# servo_controller.net
KiCad netlist of a schematic drawn in EAGLE
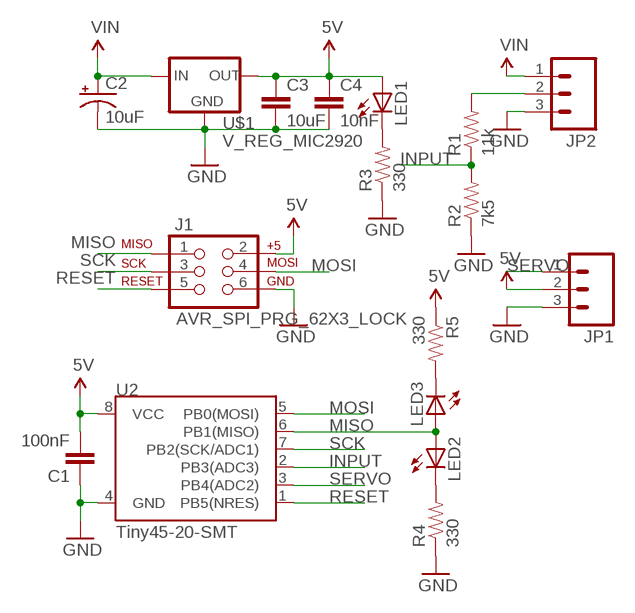
[diagram p0: schematic, sheet 1]

(export (version "E")
  (design (tool "Eeschema 10.0.6"))
  (components
    (comp (ref "C1")
      (value "100nF")
      (footprint "eagle-import:0603-CAP")
      (libsource (lib "eagle-import") (part "CAP0603-CAP"))
    )
    (comp (ref "C2")
      (value "10uF")
      (footprint "eagle-import:PANASONIC_B")
      (libsource (lib "eagle-import") (part "CPOL-USB"))
    )
    (comp (ref "C3")
      (value "10uF")
      (footprint "eagle-import:0603-CAP")
      (libsource (lib "eagle-import") (part "CAP0603-CAP"))
    )
    (comp (ref "C4")
      (value "10nF")
      (footprint "eagle-import:0603-CAP")
      (libsource (lib "eagle-import") (part "CAP0603-CAP"))
    )
    (comp (ref "J1")
      (value "AVR_SPI_PRG_62X3_LOCK")
      (footprint "eagle-import:2X3_LOCK")
      (libsource (lib "eagle-import") (part "AVR_SPI_PRG_62X3_LOCK"))
    )
    (comp (ref "JP1")
      (value "M03LOCK")
      (footprint "eagle-import:1X03_LOCK")
      (libsource (lib "eagle-import") (part "M03LOCK"))
    )
    (comp (ref "JP2")
      (value "M03POLAR_LOCK")
      (footprint "eagle-import:MOLEX-1X3_LOCK")
      (libsource (lib "eagle-import") (part "M03POLAR_LOCK"))
    )
    (comp (ref "LED1")
      (value "LED0603")
      (footprint "eagle-import:LED-0603")
      (libsource (lib "eagle-import") (part "LED0603"))
    )
    (comp (ref "LED2")
      (value "LED0603")
      (footprint "eagle-import:LED-0603")
      (libsource (lib "eagle-import") (part "LED0603"))
    )
    (comp (ref "LED3")
      (value "LED0603")
      (footprint "eagle-import:LED-0603")
      (libsource (lib "eagle-import") (part "LED0603"))
    )
    (comp (ref "R1")
      (value "11k")
      (footprint "eagle-import:0603-RES")
      (libsource (lib "eagle-import") (part "RESISTOR0603"))
    )
    (comp (ref "R2")
      (value "7k5")
      (footprint "eagle-import:0603-RES")
      (libsource (lib "eagle-import") (part "RESISTOR0603"))
    )
    (comp (ref "R3")
      (value "330")
      (footprint "eagle-import:0603-RES")
      (libsource (lib "eagle-import") (part "RESISTOR0603"))
    )
    (comp (ref "R4")
      (value "330")
      (footprint "eagle-import:0603-RES")
      (libsource (lib "eagle-import") (part "RESISTOR0603"))
    )
    (comp (ref "R5")
      (value "330")
      (footprint "eagle-import:0603-RES")
      (libsource (lib "eagle-import") (part "RESISTOR0603"))
    )
    (comp (ref "U$1")
      (value "V_REG_MIC2920")
      (footprint "eagle-import:SOT223")
      (libsource (lib "eagle-import") (part "V_REG_MIC2920"))
    )
    (comp (ref "U2")
      (value "Tiny45-20-SMT")
      (footprint "eagle-import:SO08-EIAJ")
      (libsource (lib "eagle-import") (part "ATTINY45TINY45-20-SMT"))
    )
  )
  (nets
    (net (code "1") (name "/INPUT") (class "Default")
      (node (ref "R1") (pin "1") (pinfunction "1_1") (pintype "passive"))
      (node (ref "R2") (pin "2") (pinfunction "2_2") (pintype "passive"))
      (node (ref "U2") (pin "2") (pinfunction "PB3(ADC3)_2") (pintype "bidirectional"))
    )
    (net (code "2") (name "/MISO") (class "Default")
      (node (ref "J1") (pin "1") (pinfunction "1_1") (pintype "passive"))
      (node (ref "LED2") (pin "A") (pinfunction "A_A") (pintype "passive"))
      (node (ref "LED3") (pin "A") (pinfunction "A_A") (pintype "passive"))
      (node (ref "U2") (pin "6") (pinfunction "PB1(MISO)_6") (pintype "bidirectional"))
    )
    (net (code "3") (name "/MOSI") (class "Default")
      (node (ref "J1") (pin "4") (pinfunction "4_4") (pintype "passive"))
      (node (ref "U2") (pin "5") (pinfunction "PB0(MOSI)_5") (pintype "bidirectional"))
    )
    (net (code "4") (name "/RESET") (class "Default")
      (node (ref "J1") (pin "5") (pinfunction "5_5") (pintype "passive"))
      (node (ref "U2") (pin "1") (pinfunction "PB5(NRES)_1") (pintype "bidirectional"))
    )
    (net (code "5") (name "/SCK") (class "Default")
      (node (ref "J1") (pin "3") (pinfunction "3_3") (pintype "passive"))
      (node (ref "U2") (pin "7") (pinfunction "PB2(SCK/ADC1)_7") (pintype "bidirectional"))
    )
    (net (code "6") (name "/SERVO") (class "Default")
      (node (ref "JP1") (pin "1") (pinfunction "1_1") (pintype "passive"))
      (node (ref "U2") (pin "3") (pinfunction "PB4(ADC2)_3") (pintype "bidirectional"))
    )
    (net (code "7") (name "5V") (class "Default")
      (node (ref "C1") (pin "2") (pinfunction "2_2") (pintype "passive"))
      (node (ref "C3") (pin "1") (pinfunction "1_1") (pintype "passive"))
      (node (ref "C4") (pin "1") (pinfunction "1_1") (pintype "passive"))
      (node (ref "J1") (pin "2") (pinfunction "2_2") (pintype "passive"))
      (node (ref "JP1") (pin "2") (pinfunction "2_2") (pintype "passive"))
      (node (ref "LED1") (pin "A") (pinfunction "A_A") (pintype "passive"))
      (node (ref "R5") (pin "1") (pinfunction "1_1") (pintype "passive"))
      (node (ref "U$1") (pin "3") (pinfunction "OUT_3") (pintype "output"))
      (node (ref "U2") (pin "8") (pinfunction "VCC_8") (pintype "bidirectional"))
    )
    (net (code "8") (name "GND") (class "Default")
      (node (ref "C1") (pin "1") (pinfunction "1_1") (pintype "passive"))
      (node (ref "C2") (pin "-") (pinfunction "-_-") (pintype "passive"))
      (node (ref "C3") (pin "2") (pinfunction "2_2") (pintype "passive"))
      (node (ref "C4") (pin "2") (pinfunction "2_2") (pintype "passive"))
      (node (ref "J1") (pin "6") (pinfunction "6_6") (pintype "passive"))
      (node (ref "JP1") (pin "3") (pinfunction "3_3") (pintype "passive"))
      (node (ref "JP2") (pin "3") (pinfunction "3_3") (pintype "passive"))
      (node (ref "R2") (pin "1") (pinfunction "1_1") (pintype "passive"))
      (node (ref "R3") (pin "1") (pinfunction "1_1") (pintype "passive"))
      (node (ref "R4") (pin "1") (pinfunction "1_1") (pintype "passive"))
      (node (ref "U$1") (pin "2") (pinfunction "GND_2") (pintype "input"))
      (node (ref "U2") (pin "4") (pinfunction "GND_4") (pintype "bidirectional"))
    )
    (net (code "9") (name "Net-(JP2-Pad2)") (class "Default")
      (node (ref "JP2") (pin "2") (pinfunction "2_2") (pintype "passive"))
      (node (ref "R1") (pin "2") (pinfunction "2_2") (pintype "passive"))
    )
    (net (code "10") (name "Net-(LED1-PadC)") (class "Default")
      (node (ref "LED1") (pin "C") (pinfunction "C_C") (pintype "passive"))
      (node (ref "R3") (pin "2") (pinfunction "2_2") (pintype "passive"))
    )
    (net (code "11") (name "Net-(LED2-PadC)") (class "Default")
      (node (ref "LED2") (pin "C") (pinfunction "C_C") (pintype "passive"))
      (node (ref "R4") (pin "2") (pinfunction "2_2") (pintype "passive"))
    )
    (net (code "12") (name "Net-(LED3-PadC)") (class "Default")
      (node (ref "LED3") (pin "C") (pinfunction "C_C") (pintype "passive"))
      (node (ref "R5") (pin "2") (pinfunction "2_2") (pintype "passive"))
    )
    (net (code "13") (name "VIN") (class "Default")
      (node (ref "C2") (pin "+") (pinfunction "+_+") (pintype "passive"))
      (node (ref "JP2") (pin "1") (pinfunction "1_1") (pintype "passive"))
      (node (ref "U$1") (pin "1") (pinfunction "IN_1") (pintype "input"))
    )
  )
)
